# Decodificador_de_ppm.net
KiCad netlist of a schematic drawn in EAGLE
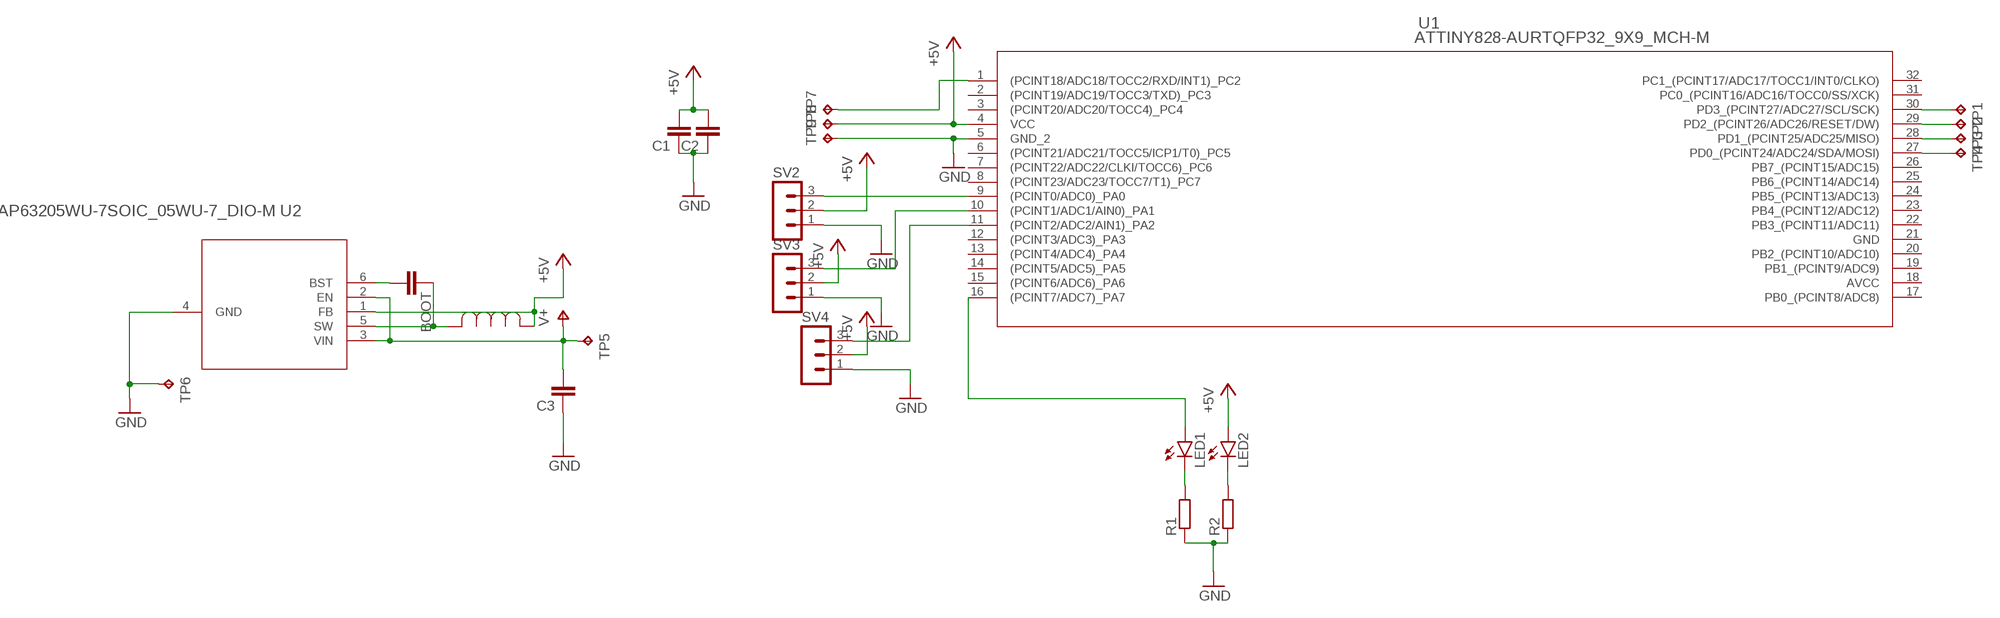
[diagram p0: schematic, sheet 1]

(export (version "E")
  (design (tool "Eeschema 10.0.6"))
  (components
    (comp (ref "BOOT")
      (value "C-EUC0402")
      (footprint "eagle-import:C0402")
      (libsource (lib "eagle-import") (part "C-EUC0402"))
    )
    (comp (ref "C1")
      (value "C-EUC0805")
      (footprint "eagle-import:C0805")
      (libsource (lib "eagle-import") (part "C-EUC0805"))
    )
    (comp (ref "C2")
      (value "C-EUC0805")
      (footprint "eagle-import:C0805")
      (libsource (lib "eagle-import") (part "C-EUC0805"))
    )
    (comp (ref "C3")
      (value "C-EUC0805")
      (footprint "eagle-import:C0805")
      (libsource (lib "eagle-import") (part "C-EUC0805"))
    )
    (comp (ref "LED1")
      (value "LEDCHIP-LED0603")
      (footprint "eagle-import:CHIP-LED0603")
      (libsource (lib "eagle-import") (part "LEDCHIP-LED0603"))
    )
    (comp (ref "LED2")
      (value "LEDCHIP-LED0603")
      (footprint "eagle-import:CHIP-LED0603")
      (libsource (lib "eagle-import") (part "LEDCHIP-LED0603"))
    )
    (comp (ref "R1")
      (value "R-EU_R0805")
      (footprint "eagle-import:R0805")
      (libsource (lib "eagle-import") (part "R-EU_R0805"))
    )
    (comp (ref "R2")
      (value "R-EU_R0805")
      (footprint "eagle-import:R0805")
      (libsource (lib "eagle-import") (part "R-EU_R0805"))
    )
    (comp (ref "SV2")
      (value "MA03-1")
      (footprint "eagle-import:MA03-1")
      (libsource (lib "eagle-import") (part "MA03-1"))
    )
    (comp (ref "SV3")
      (value "MA03-1")
      (footprint "eagle-import:MA03-1")
      (libsource (lib "eagle-import") (part "MA03-1"))
    )
    (comp (ref "SV4")
      (value "MA03-1")
      (footprint "eagle-import:MA03-1")
      (libsource (lib "eagle-import") (part "MA03-1"))
    )
    (comp (ref "TP1")
      (value "TPB1,27")
      (footprint "eagle-import:B1,27")
      (libsource (lib "eagle-import") (part "TPB1,27"))
    )
    (comp (ref "TP2")
      (value "TPB1,27")
      (footprint "eagle-import:B1,27")
      (libsource (lib "eagle-import") (part "TPB1,27"))
    )
    (comp (ref "TP3")
      (value "TPB1,27")
      (footprint "eagle-import:B1,27")
      (libsource (lib "eagle-import") (part "TPB1,27"))
    )
    (comp (ref "TP4")
      (value "TPB1,27")
      (footprint "eagle-import:B1,27")
      (libsource (lib "eagle-import") (part "TPB1,27"))
    )
    (comp (ref "TP5")
      (value "TPTP19SQ")
      (footprint "eagle-import:TP19SQ")
      (libsource (lib "eagle-import") (part "TPTP19SQ"))
    )
    (comp (ref "TP6")
      (value "TPTP19SQ")
      (footprint "eagle-import:TP19SQ")
      (libsource (lib "eagle-import") (part "TPTP19SQ"))
    )
    (comp (ref "TP7")
      (value "TPTP19SQ")
      (footprint "eagle-import:TP19SQ")
      (libsource (lib "eagle-import") (part "TPTP19SQ"))
    )
    (comp (ref "TP8")
      (value "TPTP19SQ")
      (footprint "eagle-import:TP19SQ")
      (libsource (lib "eagle-import") (part "TPTP19SQ"))
    )
    (comp (ref "TP9")
      (value "TPTP19SQ")
      (footprint "eagle-import:TP19SQ")
      (libsource (lib "eagle-import") (part "TPTP19SQ"))
    )
    (comp (ref "U$2")
      (value "INDUCTOR4.7")
      (footprint "eagle-import:IND_NRS5030T100MMGJ_TAY")
      (libsource (lib "eagle-import") (part "INDUCTOR4.7"))
    )
    (comp (ref "U1")
      (value "ATTINY828-AURTQFP32_9X9_MCH-M")
      (footprint "eagle-import:TQFP32_9X9_MCH-M")
      (fields
        (field (name "MANUFACTURER_PART_NUMBER") "ATTINY828-AUR")
        (field (name "COPYRIGHT") "Copyright (C) 2018 Accelerated Designs. All rights reserved")
      )
      (libsource (lib "eagle-import") (part "ATTINY828-AURTQFP32_9X9_MCH-M"))
    )
    (comp (ref "U2")
      (value "AP63205WU-7SOIC_05WU-7_DIO-M")
      (footprint "eagle-import:SOIC_05WU-7_DIO-M")
      (fields
        (field (name "MANUFACTURER_PART_NUMBER") "AP63205WU-7")
        (field (name "COPYRIGHT") "Copyright (C) 2018 Accelerated Designs. All rights reserved")
      )
      (libsource (lib "eagle-import") (part "AP63205WU-7SOIC_05WU-7_DIO-M"))
    )
  )
  (nets
    (net (code "1") (name "+5V") (class "Default")
      (node (ref "C1") (pin "2") (pinfunction "2_2") (pintype "passive"))
      (node (ref "C2") (pin "2") (pinfunction "2_2") (pintype "passive"))
      (node (ref "LED2") (pin "A") (pinfunction "A_A") (pintype "passive"))
      (node (ref "SV2") (pin "2") (pinfunction "2_2") (pintype "passive"))
      (node (ref "SV3") (pin "2") (pinfunction "2_2") (pintype "passive"))
      (node (ref "SV4") (pin "2") (pinfunction "2_2") (pintype "passive"))
      (node (ref "TP8") (pin "TP") (pinfunction "TP_TP") (pintype "input"))
      (node (ref "U$2") (pin "1") (pinfunction "1_1") (pintype "passive"))
      (node (ref "U1") (pin "4") (pinfunction "VCC_4") (pintype "power_in"))
      (node (ref "U2") (pin "1") (pinfunction "FB_1") (pintype "passive"))
    )
    (net (code "2") (name "GND") (class "Default")
      (node (ref "C1") (pin "1") (pinfunction "1_1") (pintype "passive"))
      (node (ref "C2") (pin "1") (pinfunction "1_1") (pintype "passive"))
      (node (ref "C3") (pin "1") (pinfunction "1_1") (pintype "passive"))
      (node (ref "R1") (pin "1") (pinfunction "1_1") (pintype "passive"))
      (node (ref "R2") (pin "1") (pinfunction "1_1") (pintype "passive"))
      (node (ref "SV2") (pin "1") (pinfunction "1_1") (pintype "passive"))
      (node (ref "SV3") (pin "1") (pinfunction "1_1") (pintype "passive"))
      (node (ref "SV4") (pin "1") (pinfunction "1_1") (pintype "passive"))
      (node (ref "TP6") (pin "TP") (pinfunction "TP_TP") (pintype "input"))
      (node (ref "TP9") (pin "TP") (pinfunction "TP_TP") (pintype "input"))
      (node (ref "U1") (pin "5") (pinfunction "GND_2_5") (pintype "passive"))
      (node (ref "U2") (pin "4") (pinfunction "GND_4") (pintype "passive"))
    )
    (net (code "3") (name "Net-(LED1-PadC)") (class "Default")
      (node (ref "LED1") (pin "C") (pinfunction "C_C") (pintype "passive"))
      (node (ref "R1") (pin "2") (pinfunction "2_2") (pintype "passive"))
    )
    (net (code "4") (name "Net-(LED2-PadC)") (class "Default")
      (node (ref "LED2") (pin "C") (pinfunction "C_C") (pintype "passive"))
      (node (ref "R2") (pin "2") (pinfunction "2_2") (pintype "passive"))
    )
    (net (code "5") (name "Net-(U1-(PCINT0{slash}ADC0)_PA0)") (class "Default")
      (node (ref "SV2") (pin "3") (pinfunction "3_3") (pintype "passive"))
      (node (ref "U1") (pin "9") (pinfunction "(PCINT0/ADC0)_PA0_9") (pintype "bidirectional"))
    )
    (net (code "6") (name "Net-(U1-(PCINT1{slash}ADC1{slash}AIN0)_PA1)") (class "Default")
      (node (ref "SV3") (pin "3") (pinfunction "3_3") (pintype "passive"))
      (node (ref "U1") (pin "10") (pinfunction "(PCINT1/ADC1/AIN0)_PA1_10") (pintype "bidirectional"))
    )
    (net (code "7") (name "Net-(U1-(PCINT2{slash}ADC2{slash}AIN1)_PA2)") (class "Default")
      (node (ref "SV4") (pin "3") (pinfunction "3_3") (pintype "passive"))
      (node (ref "U1") (pin "11") (pinfunction "(PCINT2/ADC2/AIN1)_PA2_11") (pintype "input"))
    )
    (net (code "8") (name "Net-(U1-(PCINT7{slash}ADC7)_PA7)") (class "Default")
      (node (ref "LED1") (pin "A") (pinfunction "A_A") (pintype "passive"))
      (node (ref "U1") (pin "16") (pinfunction "(PCINT7/ADC7)_PA7_16") (pintype "bidirectional"))
    )
    (net (code "9") (name "Net-(U1-(PCINT18{slash}ADC18{slash}TOCC2{slash}RXD{slash}INT1)_PC2)") (class "Default")
      (node (ref "TP7") (pin "TP") (pinfunction "TP_TP") (pintype "input"))
      (node (ref "U1") (pin "1") (pinfunction "(PCINT18/ADC18/TOCC2/RXD/INT1)_PC2_1") (pintype "bidirectional"))
    )
    (net (code "10") (name "Net-(U1-PD0_(PCINT24{slash}ADC24{slash}SDA{slash}MOSI))") (class "Default")
      (node (ref "TP4") (pin "TP") (pinfunction "TP_TP") (pintype "input"))
      (node (ref "U1") (pin "27") (pinfunction "PD0_(PCINT24/ADC24/SDA/MOSI)_27") (pintype "bidirectional"))
    )
    (net (code "11") (name "Net-(U1-PD1_(PCINT25{slash}ADC25{slash}MISO))") (class "Default")
      (node (ref "TP3") (pin "TP") (pinfunction "TP_TP") (pintype "input"))
      (node (ref "U1") (pin "28") (pinfunction "PD1_(PCINT25/ADC25/MISO)_28") (pintype "bidirectional"))
    )
    (net (code "12") (name "Net-(U1-PD2_(PCINT26{slash}ADC26{slash}RESET{slash}DW))") (class "Default")
      (node (ref "TP2") (pin "TP") (pinfunction "TP_TP") (pintype "input"))
      (node (ref "U1") (pin "29") (pinfunction "PD2_(PCINT26/ADC26/RESET/DW)_29") (pintype "bidirectional"))
    )
    (net (code "13") (name "Net-(U1-PD3_(PCINT27{slash}ADC27{slash}SCL{slash}SCK))") (class "Default")
      (node (ref "TP1") (pin "TP") (pinfunction "TP_TP") (pintype "input"))
      (node (ref "U1") (pin "30") (pinfunction "PD3_(PCINT27/ADC27/SCL/SCK)_30") (pintype "bidirectional"))
    )
    (net (code "14") (name "Net-(U2-BST)") (class "Default")
      (node (ref "BOOT") (pin "2") (pinfunction "2_2") (pintype "passive"))
      (node (ref "U2") (pin "6") (pinfunction "BST_6") (pintype "passive"))
    )
    (net (code "15") (name "Net-(U2-SW)") (class "Default")
      (node (ref "BOOT") (pin "1") (pinfunction "1_1") (pintype "passive"))
      (node (ref "U$2") (pin "2") (pinfunction "2_2") (pintype "passive"))
      (node (ref "U2") (pin "5") (pinfunction "SW_5") (pintype "passive"))
    )
    (net (code "16") (name "V+") (class "Default")
      (node (ref "C3") (pin "2") (pinfunction "2_2") (pintype "passive"))
      (node (ref "TP5") (pin "TP") (pinfunction "TP_TP") (pintype "input"))
      (node (ref "U2") (pin "2") (pinfunction "EN_2") (pintype "passive"))
      (node (ref "U2") (pin "3") (pinfunction "VIN_3") (pintype "passive"))
    )
    (net (code "17") (name "unconnected-(U1-(PCINT3{slash}ADC3)_PA3-Pad12)") (class "Default")
      (node (ref "U1") (pin "12") (pinfunction "(PCINT3/ADC3)_PA3_12") (pintype "bidirectional"))
    )
    (net (code "18") (name "unconnected-(U1-(PCINT4{slash}ADC4)_PA4-Pad13)") (class "Default")
      (node (ref "U1") (pin "13") (pinfunction "(PCINT4/ADC4)_PA4_13") (pintype "bidirectional"))
    )
    (net (code "19") (name "unconnected-(U1-(PCINT5{slash}ADC5)_PA5-Pad14)") (class "Default")
      (node (ref "U1") (pin "14") (pinfunction "(PCINT5/ADC5)_PA5_14") (pintype "bidirectional"))
    )
    (net (code "20") (name "unconnected-(U1-(PCINT6{slash}ADC6)_PA6-Pad15)") (class "Default")
      (node (ref "U1") (pin "15") (pinfunction "(PCINT6/ADC6)_PA6_15") (pintype "bidirectional"))
    )
    (net (code "21") (name "unconnected-(U1-(PCINT19{slash}ADC19{slash}TOCC3{slash}TXD)_PC3-Pad2)") (class "Default")
      (node (ref "U1") (pin "2") (pinfunction "(PCINT19/ADC19/TOCC3/TXD)_PC3_2") (pintype "bidirectional"))
    )
    (net (code "22") (name "unconnected-(U1-(PCINT20{slash}ADC20{slash}TOCC4)_PC4-Pad3)") (class "Default")
      (node (ref "U1") (pin "3") (pinfunction "(PCINT20/ADC20/TOCC4)_PC4_3") (pintype "bidirectional"))
    )
    (net (code "23") (name "unconnected-(U1-(PCINT21{slash}ADC21{slash}TOCC5{slash}ICP1{slash}T0)_PC5-Pad6)") (class "Default")
      (node (ref "U1") (pin "6") (pinfunction "(PCINT21/ADC21/TOCC5/ICP1/T0)_PC5_6") (pintype "bidirectional"))
    )
    (net (code "24") (name "unconnected-(U1-(PCINT22{slash}ADC22{slash}CLKI{slash}TOCC6)_PC6-Pad7)") (class "Default")
      (node (ref "U1") (pin "7") (pinfunction "(PCINT22/ADC22/CLKI/TOCC6)_PC6_7") (pintype "bidirectional"))
    )
    (net (code "25") (name "unconnected-(U1-(PCINT23{slash}ADC23{slash}TOCC7{slash}T1)_PC7-Pad8)") (class "Default")
      (node (ref "U1") (pin "8") (pinfunction "(PCINT23/ADC23/TOCC7/T1)_PC7_8") (pintype "bidirectional"))
    )
    (net (code "26") (name "unconnected-(U1-AVCC-Pad18)") (class "Default")
      (node (ref "U1") (pin "18") (pinfunction "AVCC_18") (pintype "passive"))
    )
    (net (code "27") (name "unconnected-(U1-GND-Pad21)") (class "Default")
      (node (ref "U1") (pin "21") (pinfunction "GND_21") (pintype "passive"))
    )
    (net (code "28") (name "unconnected-(U1-PB0_(PCINT8{slash}ADC8)-Pad17)") (class "Default")
      (node (ref "U1") (pin "17") (pinfunction "PB0_(PCINT8/ADC8)_17") (pintype "bidirectional"))
    )
    (net (code "29") (name "unconnected-(U1-PB1_(PCINT9{slash}ADC9)-Pad19)") (class "Default")
      (node (ref "U1") (pin "19") (pinfunction "PB1_(PCINT9/ADC9)_19") (pintype "bidirectional"))
    )
    (net (code "30") (name "unconnected-(U1-PB2_(PCINT10{slash}ADC10)-Pad20)") (class "Default")
      (node (ref "U1") (pin "20") (pinfunction "PB2_(PCINT10/ADC10)_20") (pintype "bidirectional"))
    )
    (net (code "31") (name "unconnected-(U1-PB3_(PCINT11{slash}ADC11)-Pad22)") (class "Default")
      (node (ref "U1") (pin "22") (pinfunction "PB3_(PCINT11/ADC11)_22") (pintype "bidirectional"))
    )
    (net (code "32") (name "unconnected-(U1-PB4_(PCINT12{slash}ADC12)-Pad23)") (class "Default")
      (node (ref "U1") (pin "23") (pinfunction "PB4_(PCINT12/ADC12)_23") (pintype "bidirectional"))
    )
    (net (code "33") (name "unconnected-(U1-PB5_(PCINT13{slash}ADC13)-Pad24)") (class "Default")
      (node (ref "U1") (pin "24") (pinfunction "PB5_(PCINT13/ADC13)_24") (pintype "bidirectional"))
    )
    (net (code "34") (name "unconnected-(U1-PB6_(PCINT14{slash}ADC14)-Pad25)") (class "Default")
      (node (ref "U1") (pin "25") (pinfunction "PB6_(PCINT14/ADC14)_25") (pintype "bidirectional"))
    )
    (net (code "35") (name "unconnected-(U1-PB7_(PCINT15{slash}ADC15)-Pad26)") (class "Default")
      (node (ref "U1") (pin "26") (pinfunction "PB7_(PCINT15/ADC15)_26") (pintype "bidirectional"))
    )
    (net (code "36") (name "unconnected-(U1-PC0_(PCINT16{slash}ADC16{slash}TOCC0{slash}SS{slash}XCK)-Pad31)") (class "Default")
      (node (ref "U1") (pin "31") (pinfunction "PC0_(PCINT16/ADC16/TOCC0/SS/XCK)_31") (pintype "bidirectional"))
    )
    (net (code "37") (name "unconnected-(U1-PC1_(PCINT17{slash}ADC17{slash}TOCC1{slash}INT0{slash}CLKO)-Pad32)") (class "Default")
      (node (ref "U1") (pin "32") (pinfunction "PC1_(PCINT17/ADC17/TOCC1/INT0/CLKO)_32") (pintype "bidirectional"))
    )
  )
)
